# Placa_principal.net
KiCad netlist of a schematic drawn in EAGLE
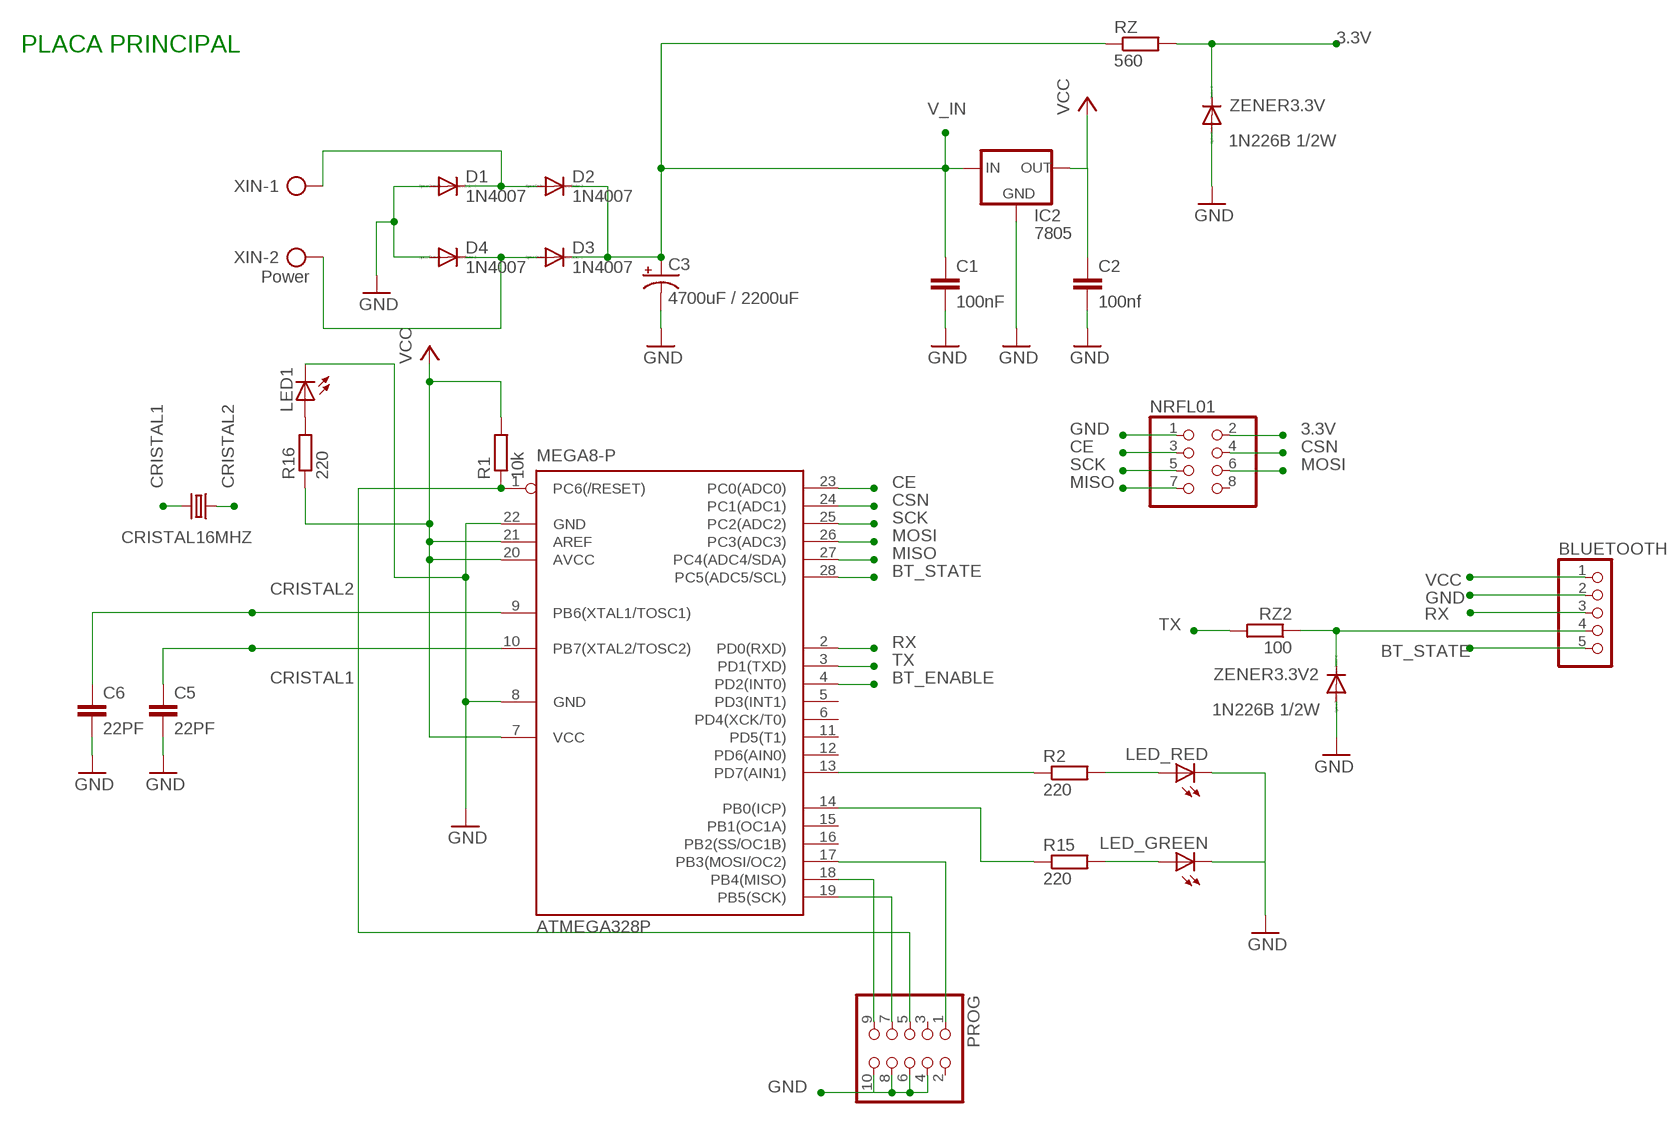
[diagram p0: schematic, sheet 1]

(export (version "E")
  (design (tool "Eeschema 10.0.6"))
  (components
    (comp (ref "ATMEGA328P")
      (value "MEGA8-P")
      (footprint "eagle-import:DIL28-3")
      (libsource (lib "eagle-import") (part "MEGA8-P"))
    )
    (comp (ref "BLUETOOTH")
      (value "PINHD-1X5")
      (footprint "eagle-import:1X05")
      (libsource (lib "eagle-import") (part "PINHD-1X5"))
    )
    (comp (ref "C1")
      (value "100nF")
      (footprint "eagle-import:C050-025X075")
      (libsource (lib "eagle-import") (part "C-EU050-025X075"))
    )
    (comp (ref "C2")
      (value "100nf")
      (footprint "eagle-import:C050-025X075")
      (libsource (lib "eagle-import") (part "C-EU050-025X075"))
    )
    (comp (ref "C3")
      (value "4700uF / 2200uF")
      (footprint "eagle-import:E7,5-16")
      (libsource (lib "eagle-import") (part "CPOL-USE7.5-16"))
    )
    (comp (ref "C5")
      (value "22PF")
      (footprint "eagle-import:C050-024X044")
      (libsource (lib "eagle-import") (part "C-EU050-024X044"))
    )
    (comp (ref "C6")
      (value "22PF")
      (footprint "eagle-import:C050-024X044")
      (libsource (lib "eagle-import") (part "C-EU050-024X044"))
    )
    (comp (ref "CRISTAL16MHZ")
      (value "CRYSTALHC49S")
      (footprint "eagle-import:HC49_S")
      (libsource (lib "eagle-import") (part "CRYSTALHC49S"))
    )
    (comp (ref "D1")
      (value "1N4007")
      (footprint "eagle-import:DO41-10")
      (libsource (lib "eagle-import") (part "1N4004"))
    )
    (comp (ref "D2")
      (value "1N4007")
      (footprint "eagle-import:DO41-10")
      (libsource (lib "eagle-import") (part "1N4004"))
    )
    (comp (ref "D3")
      (value "1N4007")
      (footprint "eagle-import:DO41-10")
      (libsource (lib "eagle-import") (part "1N4004"))
    )
    (comp (ref "D4")
      (value "1N4007")
      (footprint "eagle-import:DO41-10")
      (libsource (lib "eagle-import") (part "1N4004"))
    )
    (comp (ref "IC2")
      (value "7805")
      (footprint "eagle-import:78XXL")
      (libsource (lib "eagle-import") (part "78XXL"))
    )
    (comp (ref "LED1")
      (value "LED5MM")
      (footprint "eagle-import:LED5MM")
      (libsource (lib "eagle-import") (part "LED5MM"))
    )
    (comp (ref "LED_GREEN")
      (value "LED5MM")
      (footprint "eagle-import:LED5MM")
      (libsource (lib "eagle-import") (part "LED5MM"))
    )
    (comp (ref "LED_RED")
      (value "LED5MM")
      (footprint "eagle-import:LED5MM")
      (libsource (lib "eagle-import") (part "LED5MM"))
    )
    (comp (ref "NRFL01")
      (value "PINHD-2X4")
      (footprint "eagle-import:2X04")
      (libsource (lib "eagle-import") (part "PINHD-2X4"))
    )
    (comp (ref "PROG")
      (value "PINHD-2X5")
      (footprint "eagle-import:2X05")
      (libsource (lib "eagle-import") (part "PINHD-2X5"))
    )
    (comp (ref "R1")
      (value "10k")
      (footprint "eagle-import:0207_10")
      (libsource (lib "eagle-import") (part "R-EU_0207/10"))
    )
    (comp (ref "R2")
      (value "220")
      (footprint "eagle-import:0207_10")
      (libsource (lib "eagle-import") (part "R-EU_0207/10"))
    )
    (comp (ref "R15")
      (value "220")
      (footprint "eagle-import:0207_10")
      (libsource (lib "eagle-import") (part "R-EU_0207/10"))
    )
    (comp (ref "R16")
      (value "220")
      (footprint "eagle-import:0309_10")
      (libsource (lib "eagle-import") (part "R-EU_0309/10"))
    )
    (comp (ref "RZ")
      (value "560")
      (footprint "eagle-import:0207_10")
      (libsource (lib "eagle-import") (part "R-EU_0207/10"))
    )
    (comp (ref "RZ2")
      (value "100")
      (footprint "eagle-import:0207_10")
      (libsource (lib "eagle-import") (part "R-EU_0207/10"))
    )
    (comp (ref "XIN")
      (value "Power")
      (footprint "eagle-import:AK500_2")
      (libsource (lib "eagle-import") (part "AK500/2"))
    )
    (comp (ref "ZENER3.3V")
      (value "1N226B 1/2W")
      (footprint "eagle-import:DO35-10")
      (libsource (lib "eagle-import") (part "1N4148DO35-10"))
    )
    (comp (ref "ZENER3.3V2")
      (value "1N226B 1/2W")
      (footprint "eagle-import:DO35-10")
      (libsource (lib "eagle-import") (part "1N4148DO35-10"))
    )
  )
  (nets
    (net (code "1") (name "/3.3V") (class "Default")
      (node (ref "NRFL01") (pin "2") (pinfunction "2_2") (pintype "passive"))
      (node (ref "RZ") (pin "2") (pinfunction "2_2") (pintype "passive"))
      (node (ref "ZENER3.3V") (pin "C") (pinfunction "C_C") (pintype "passive"))
    )
    (net (code "2") (name "/BT_ENABLE") (class "Default")
      (node (ref "ATMEGA328P") (pin "4") (pinfunction "PD2(INT0)_4") (pintype "bidirectional"))
    )
    (net (code "3") (name "/BT_STATE") (class "Default")
      (node (ref "ATMEGA328P") (pin "28") (pinfunction "PC5(ADC5/SCL)_28") (pintype "bidirectional"))
      (node (ref "BLUETOOTH") (pin "5") (pinfunction "5_5") (pintype "passive"))
    )
    (net (code "4") (name "/CE") (class "Default")
      (node (ref "ATMEGA328P") (pin "23") (pinfunction "PC0(ADC0)_23") (pintype "bidirectional"))
      (node (ref "NRFL01") (pin "3") (pinfunction "3_3") (pintype "passive"))
    )
    (net (code "5") (name "/CRISTAL1") (class "Default")
      (node (ref "ATMEGA328P") (pin "10") (pinfunction "PB7(XTAL2/TOSC2)_10") (pintype "bidirectional"))
      (node (ref "C5") (pin "1") (pinfunction "1_1") (pintype "passive"))
      (node (ref "CRISTAL16MHZ") (pin "2") (pinfunction "2_2") (pintype "passive"))
    )
    (net (code "6") (name "/CRISTAL2") (class "Default")
      (node (ref "ATMEGA328P") (pin "9") (pinfunction "PB6(XTAL1/TOSC1)_9") (pintype "bidirectional"))
      (node (ref "C6") (pin "1") (pinfunction "1_1") (pintype "passive"))
      (node (ref "CRISTAL16MHZ") (pin "1") (pinfunction "1_1") (pintype "passive"))
    )
    (net (code "7") (name "/CSN") (class "Default")
      (node (ref "ATMEGA328P") (pin "24") (pinfunction "PC1(ADC1)_24") (pintype "bidirectional"))
      (node (ref "NRFL01") (pin "4") (pinfunction "4_4") (pintype "passive"))
    )
    (net (code "8") (name "/MISO") (class "Default")
      (node (ref "ATMEGA328P") (pin "27") (pinfunction "PC4(ADC4/SDA)_27") (pintype "bidirectional"))
      (node (ref "NRFL01") (pin "7") (pinfunction "7_7") (pintype "passive"))
    )
    (net (code "9") (name "/MOSI") (class "Default")
      (node (ref "ATMEGA328P") (pin "26") (pinfunction "PC3(ADC3)_26") (pintype "bidirectional"))
      (node (ref "NRFL01") (pin "6") (pinfunction "6_6") (pintype "passive"))
    )
    (net (code "10") (name "/RX") (class "Default")
      (node (ref "ATMEGA328P") (pin "2") (pinfunction "PD0(RXD)_2") (pintype "bidirectional"))
      (node (ref "BLUETOOTH") (pin "3") (pinfunction "3_3") (pintype "passive"))
    )
    (net (code "11") (name "/SCK") (class "Default")
      (node (ref "ATMEGA328P") (pin "25") (pinfunction "PC2(ADC2)_25") (pintype "bidirectional"))
      (node (ref "NRFL01") (pin "5") (pinfunction "5_5") (pintype "passive"))
    )
    (net (code "12") (name "/TX") (class "Default")
      (node (ref "ATMEGA328P") (pin "3") (pinfunction "PD1(TXD)_3") (pintype "bidirectional"))
      (node (ref "RZ2") (pin "2") (pinfunction "2_2") (pintype "passive"))
    )
    (net (code "13") (name "/V_IN") (class "Default")
      (node (ref "C1") (pin "1") (pinfunction "1_1") (pintype "passive"))
      (node (ref "C3") (pin "+") (pinfunction "+_+") (pintype "passive"))
      (node (ref "D2") (pin "C") (pinfunction "C_C") (pintype "passive"))
      (node (ref "D3") (pin "C") (pinfunction "C_C") (pintype "passive"))
      (node (ref "IC2") (pin "IN") (pinfunction "IN_IN") (pintype "input"))
      (node (ref "RZ") (pin "1") (pinfunction "1_1") (pintype "passive"))
    )
    (net (code "14") (name "GND") (class "Default")
      (node (ref "ATMEGA328P") (pin "22") (pinfunction "GND_22") (pintype "power_in"))
      (node (ref "ATMEGA328P") (pin "8") (pinfunction "GND_8") (pintype "power_in"))
      (node (ref "BLUETOOTH") (pin "2") (pinfunction "2_2") (pintype "passive"))
      (node (ref "C1") (pin "2") (pinfunction "2_2") (pintype "passive"))
      (node (ref "C2") (pin "2") (pinfunction "2_2") (pintype "passive"))
      (node (ref "C3") (pin "-") (pinfunction "-_-") (pintype "passive"))
      (node (ref "C5") (pin "2") (pinfunction "2_2") (pintype "passive"))
      (node (ref "C6") (pin "2") (pinfunction "2_2") (pintype "passive"))
      (node (ref "D1") (pin "A") (pinfunction "A_A") (pintype "passive"))
      (node (ref "D4") (pin "A") (pinfunction "A_A") (pintype "passive"))
      (node (ref "IC2") (pin "GND") (pinfunction "GND_GND") (pintype "input"))
      (node (ref "LED1") (pin "K") (pinfunction "C_K") (pintype "passive"))
      (node (ref "LED_GREEN") (pin "K") (pinfunction "C_K") (pintype "passive"))
      (node (ref "LED_RED") (pin "K") (pinfunction "C_K") (pintype "passive"))
      (node (ref "NRFL01") (pin "1") (pinfunction "1_1") (pintype "passive"))
      (node (ref "PROG") (pin "10") (pinfunction "10_10") (pintype "passive"))
      (node (ref "PROG") (pin "4") (pinfunction "4_4") (pintype "passive"))
      (node (ref "PROG") (pin "6") (pinfunction "6_6") (pintype "passive"))
      (node (ref "PROG") (pin "8") (pinfunction "8_8") (pintype "passive"))
      (node (ref "ZENER3.3V") (pin "A") (pinfunction "A_A") (pintype "passive"))
      (node (ref "ZENER3.3V2") (pin "A") (pinfunction "A_A") (pintype "passive"))
    )
    (net (code "15") (name "Net-(ATMEGA328P-PB0(ICP))") (class "Default")
      (node (ref "ATMEGA328P") (pin "14") (pinfunction "PB0(ICP)_14") (pintype "bidirectional"))
      (node (ref "R15") (pin "1") (pinfunction "1_1") (pintype "passive"))
    )
    (net (code "16") (name "Net-(ATMEGA328P-PB3(MOSI{slash}OC2))") (class "Default")
      (node (ref "ATMEGA328P") (pin "17") (pinfunction "PB3(MOSI/OC2)_17") (pintype "bidirectional"))
      (node (ref "PROG") (pin "1") (pinfunction "1_1") (pintype "passive"))
    )
    (net (code "17") (name "Net-(ATMEGA328P-PB4(MISO))") (class "Default")
      (node (ref "ATMEGA328P") (pin "18") (pinfunction "PB4(MISO)_18") (pintype "bidirectional"))
      (node (ref "PROG") (pin "9") (pinfunction "9_9") (pintype "passive"))
    )
    (net (code "18") (name "Net-(ATMEGA328P-PB5(SCK))") (class "Default")
      (node (ref "ATMEGA328P") (pin "19") (pinfunction "PB5(SCK)_19") (pintype "bidirectional"))
      (node (ref "PROG") (pin "7") (pinfunction "7_7") (pintype "passive"))
    )
    (net (code "19") (name "Net-(ATMEGA328P-PC6({slash}RESET))") (class "Default")
      (node (ref "ATMEGA328P") (pin "1") (pinfunction "PC6(/RESET)_1") (pintype "bidirectional"))
      (node (ref "PROG") (pin "5") (pinfunction "5_5") (pintype "passive"))
      (node (ref "R1") (pin "1") (pinfunction "1_1") (pintype "passive"))
    )
    (net (code "20") (name "Net-(ATMEGA328P-PD7(AIN1))") (class "Default")
      (node (ref "ATMEGA328P") (pin "13") (pinfunction "PD7(AIN1)_13") (pintype "bidirectional"))
      (node (ref "R2") (pin "1") (pinfunction "1_1") (pintype "passive"))
    )
    (net (code "21") (name "Net-(BLUETOOTH-Pad4)") (class "Default")
      (node (ref "BLUETOOTH") (pin "4") (pinfunction "4_4") (pintype "passive"))
      (node (ref "RZ2") (pin "1") (pinfunction "1_1") (pintype "passive"))
      (node (ref "ZENER3.3V2") (pin "C") (pinfunction "C_C") (pintype "passive"))
    )
    (net (code "22") (name "Net-(LED1-PadA)") (class "Default")
      (node (ref "LED1") (pin "A") (pinfunction "A_A") (pintype "passive"))
      (node (ref "R16") (pin "2") (pinfunction "2_2") (pintype "passive"))
    )
    (net (code "23") (name "Net-(LED_GREEN-PadA)") (class "Default")
      (node (ref "LED_GREEN") (pin "A") (pinfunction "A_A") (pintype "passive"))
      (node (ref "R15") (pin "2") (pinfunction "2_2") (pintype "passive"))
    )
    (net (code "24") (name "Net-(LED_RED-PadA)") (class "Default")
      (node (ref "LED_RED") (pin "A") (pinfunction "A_A") (pintype "passive"))
      (node (ref "R2") (pin "2") (pinfunction "2_2") (pintype "passive"))
    )
    (net (code "25") (name "Net-(XINA-KL)") (class "Default")
      (node (ref "D1") (pin "C") (pinfunction "C_C") (pintype "passive"))
      (node (ref "D2") (pin "A") (pinfunction "A_A") (pintype "passive"))
      (node (ref "XIN") (pin "1") (pinfunction "KL_1") (pintype "passive"))
    )
    (net (code "26") (name "Net-(XINB-KL)") (class "Default")
      (node (ref "D3") (pin "A") (pinfunction "A_A") (pintype "passive"))
      (node (ref "D4") (pin "C") (pinfunction "C_C") (pintype "passive"))
      (node (ref "XIN") (pin "2") (pinfunction "KL_2") (pintype "passive"))
    )
    (net (code "27") (name "VCC") (class "Default")
      (node (ref "ATMEGA328P") (pin "20") (pinfunction "AVCC_20") (pintype "power_in"))
      (node (ref "ATMEGA328P") (pin "21") (pinfunction "AREF_21") (pintype "passive"))
      (node (ref "ATMEGA328P") (pin "7") (pinfunction "VCC_7") (pintype "power_in"))
      (node (ref "BLUETOOTH") (pin "1") (pinfunction "1_1") (pintype "passive"))
      (node (ref "C2") (pin "1") (pinfunction "1_1") (pintype "passive"))
      (node (ref "IC2") (pin "OUT") (pinfunction "OUT_OUT") (pintype "passive"))
      (node (ref "R1") (pin "2") (pinfunction "2_2") (pintype "passive"))
      (node (ref "R16") (pin "1") (pinfunction "1_1") (pintype "passive"))
    )
    (net (code "28") (name "unconnected-(ATMEGA328P-PB1(OC1A)-Pad15)") (class "Default")
      (node (ref "ATMEGA328P") (pin "15") (pinfunction "PB1(OC1A)_15") (pintype "bidirectional"))
    )
    (net (code "29") (name "unconnected-(ATMEGA328P-PB2(SS{slash}OC1B)-Pad16)") (class "Default")
      (node (ref "ATMEGA328P") (pin "16") (pinfunction "PB2(SS/OC1B)_16") (pintype "bidirectional"))
    )
    (net (code "30") (name "unconnected-(ATMEGA328P-PD3(INT1)-Pad5)") (class "Default")
      (node (ref "ATMEGA328P") (pin "5") (pinfunction "PD3(INT1)_5") (pintype "bidirectional"))
    )
    (net (code "31") (name "unconnected-(ATMEGA328P-PD4(XCK{slash}T0)-Pad6)") (class "Default")
      (node (ref "ATMEGA328P") (pin "6") (pinfunction "PD4(XCK/T0)_6") (pintype "bidirectional"))
    )
    (net (code "32") (name "unconnected-(ATMEGA328P-PD5(T1)-Pad11)") (class "Default")
      (node (ref "ATMEGA328P") (pin "11") (pinfunction "PD5(T1)_11") (pintype "bidirectional"))
    )
    (net (code "33") (name "unconnected-(ATMEGA328P-PD6(AIN0)-Pad12)") (class "Default")
      (node (ref "ATMEGA328P") (pin "12") (pinfunction "PD6(AIN0)_12") (pintype "bidirectional"))
    )
    (net (code "34") (name "unconnected-(NRFL01-Pad8)") (class "Default")
      (node (ref "NRFL01") (pin "8") (pinfunction "8_8") (pintype "passive"))
    )
    (net (code "35") (name "unconnected-(PROG-Pad2)") (class "Default")
      (node (ref "PROG") (pin "2") (pinfunction "2_2") (pintype "passive"))
    )
    (net (code "36") (name "unconnected-(PROG-Pad3)") (class "Default")
      (node (ref "PROG") (pin "3") (pinfunction "3_3") (pintype "passive"))
    )
  )
)
